# si1153-breakout.net
KiCad netlist of a schematic drawn in EAGLE
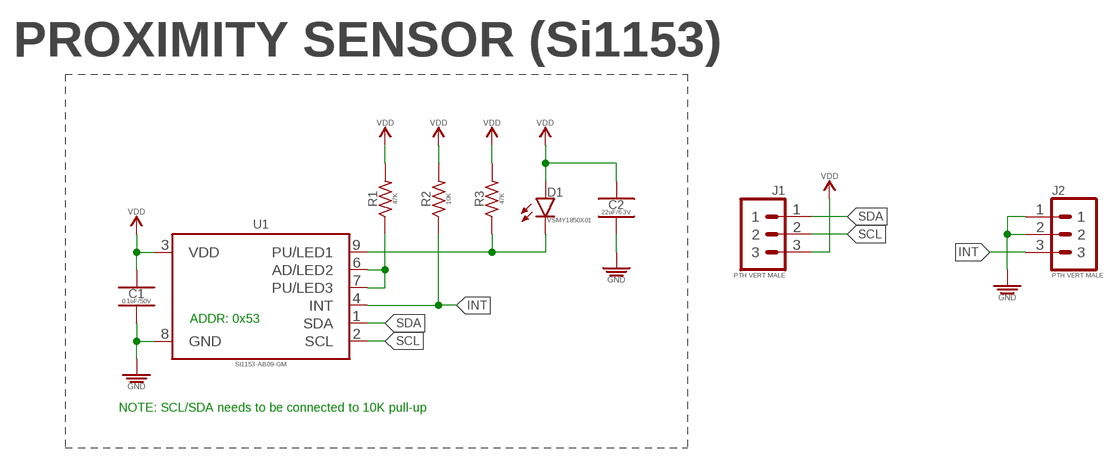
[diagram p0: schematic, sheet 1]

(export (version "E")
  (design (tool "Eeschema 10.0.6"))
  (components
    (comp (ref "C1")
      (value "0.1uF/50V")
      (footprint "eagle-import:CAPC1005X55_SMD-0402")
      (fields (field (name "MFR") "TDK Corporation") (field (name "MPN") "C1005X7R1H104K050BE"))
      (libsource (lib "eagle-import") (part "0.1UF_SMD-0402_50V-10%"))
    )
    (comp (ref "C2")
      (value "22uF/6.3V")
      (footprint "eagle-import:CAPC1005X55_SMD-0402")
      (fields (field (name "MFR") "Samsung Electro-Mechanics") (field (name "MPN") "CL05A226MQ5QUNC"))
      (libsource (lib "eagle-import") (part "22UF_SMD-0402_50V-10%"))
    )
    (comp (ref "D1")
      (value "VSMY1850X01")
      (footprint "eagle-import:LEDC2012X120_LED-0805")
      (fields (field (name "MFR") "Vishay Semiconductor Opto Division"))
      (libsource (lib "eagle-import") (part "VSMY1850X01"))
    )
    (comp (ref "J1")
      (value "PTH VERT MALE")
      (footprint "eagle-import:HDRV3W64P254_1X3_762X254X838B")
      (fields (field (name "MFR") "Sullins Connector Solutions") (field (name "MPN") "PEC03SAAN"))
      (libsource (lib "eagle-import") (part "1X03_PTH_VERT_MALE_2.54MM"))
    )
    (comp (ref "J2")
      (value "PTH VERT MALE")
      (footprint "eagle-import:HDRV3W64P254_1X3_762X254X838B")
      (fields (field (name "MFR") "Sullins Connector Solutions") (field (name "MPN") "PEC03SAAN"))
      (libsource (lib "eagle-import") (part "1X03_PTH_VERT_MALE_2.54MM"))
    )
    (comp (ref "R1")
      (value "47K")
      (footprint "eagle-import:RESC1005X35_SMD-0402")
      (fields (field (name "MFR") "Yageo") (field (name "MPN") "AC0402JR-0747KL"))
      (libsource (lib "eagle-import") (part "47KΩ_SMD-0402_1/16W-5%"))
    )
    (comp (ref "R2")
      (value "10K")
      (footprint "eagle-import:RESC1005X35_SMD-0402")
      (fields (field (name "MFR") "Yageo") (field (name "MPN") "RC0402JR-0710KP"))
      (libsource (lib "eagle-import") (part "10KΩ_SMD-0402_1/16W-5%"))
    )
    (comp (ref "R3")
      (value "47K")
      (footprint "eagle-import:RESC1005X35_SMD-0402")
      (fields (field (name "MFR") "Yageo") (field (name "MPN") "AC0402JR-0747KL"))
      (libsource (lib "eagle-import") (part "47KΩ_SMD-0402_1/16W-5%"))
    )
    (comp (ref "U1")
      (value "SI1153-AB09-GM")
      (footprint "eagle-import:QFN50P200X200X75-10N")
      (fields (field (name "MFR") "Silicon Labs"))
      (libsource (lib "eagle-import") (part "SI1135"))
    )
  )
  (nets
    (net (code "1") (name "GND") (class "Default")
      (node (ref "C1") (pin "2") (pinfunction "2_2") (pintype "passive"))
      (node (ref "C2") (pin "2") (pinfunction "2_2") (pintype "passive"))
      (node (ref "J2") (pin "1") (pinfunction "1_1") (pintype "passive"))
      (node (ref "J2") (pin "2") (pinfunction "2_2") (pintype "passive"))
      (node (ref "U1") (pin "8") (pinfunction "GND_8") (pintype "power_in"))
    )
    (net (code "2") (name "INT") (class "Default")
      (node (ref "J2") (pin "3") (pinfunction "3_3") (pintype "passive"))
      (node (ref "R2") (pin "1") (pinfunction "1_1") (pintype "passive"))
      (node (ref "U1") (pin "4") (pinfunction "INT_4") (pintype "bidirectional"))
    )
    (net (code "3") (name "Net-(U1-AD{slash}LED2)") (class "Default")
      (node (ref "R1") (pin "1") (pinfunction "1_1") (pintype "passive"))
      (node (ref "U1") (pin "6") (pinfunction "AD/LED2_6") (pintype "output"))
      (node (ref "U1") (pin "7") (pinfunction "PU/LED3_7") (pintype "output"))
    )
    (net (code "4") (name "Net-(U1-PU{slash}LED1)") (class "Default")
      (node (ref "D1") (pin "K") (pinfunction "K_K") (pintype "passive"))
      (node (ref "R3") (pin "1") (pinfunction "1_1") (pintype "passive"))
      (node (ref "U1") (pin "9") (pinfunction "PU/LED1_9") (pintype "output"))
    )
    (net (code "5") (name "SCL") (class "Default")
      (node (ref "J1") (pin "2") (pinfunction "2_2") (pintype "passive"))
      (node (ref "U1") (pin "2") (pinfunction "SCL_2") (pintype "bidirectional"))
    )
    (net (code "6") (name "SDA") (class "Default")
      (node (ref "J1") (pin "1") (pinfunction "1_1") (pintype "passive"))
      (node (ref "U1") (pin "1") (pinfunction "SDA_1") (pintype "bidirectional"))
    )
    (net (code "7") (name "VDD") (class "Default")
      (node (ref "C1") (pin "1") (pinfunction "1_1") (pintype "passive"))
      (node (ref "C2") (pin "1") (pinfunction "1_1") (pintype "passive"))
      (node (ref "D1") (pin "A") (pinfunction "A_A") (pintype "passive"))
      (node (ref "J1") (pin "3") (pinfunction "3_3") (pintype "passive"))
      (node (ref "R1") (pin "2") (pinfunction "2_2") (pintype "passive"))
      (node (ref "R2") (pin "2") (pinfunction "2_2") (pintype "passive"))
      (node (ref "R3") (pin "2") (pinfunction "2_2") (pintype "passive"))
      (node (ref "U1") (pin "3") (pinfunction "VDD_3") (pintype "power_in"))
    )
  )
)
